# meteo_board.net
KiCad netlist of a schematic drawn in EAGLE
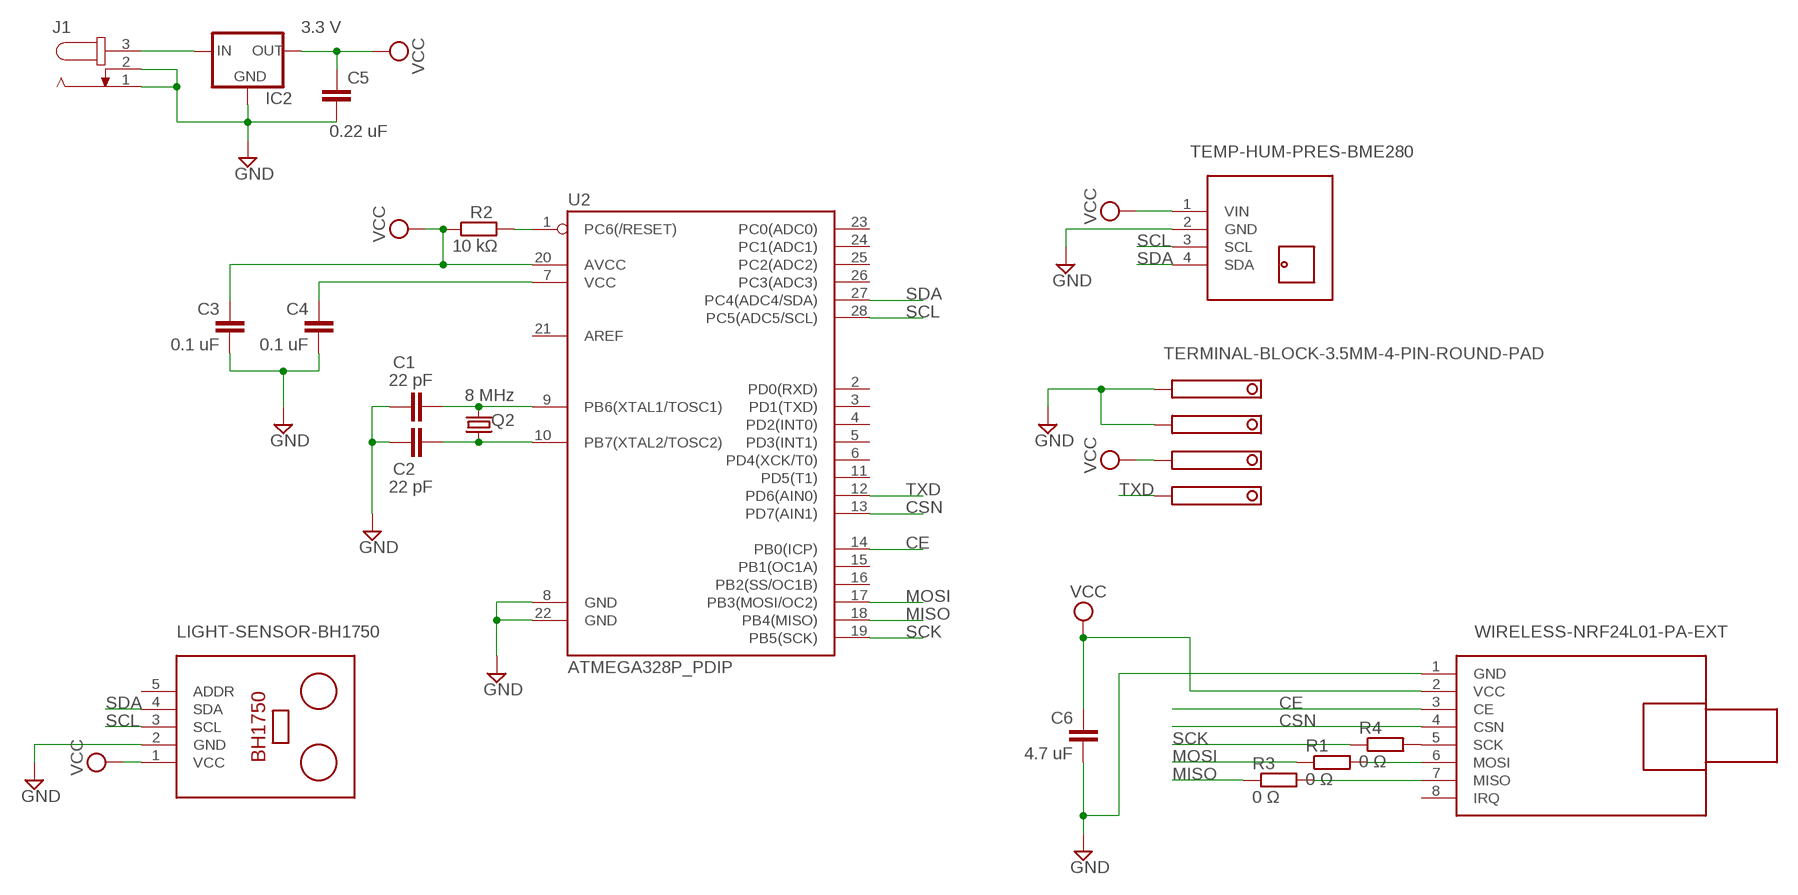
[diagram p0: schematic, sheet 1]

(export (version "E")
  (design (tool "Eeschema 10.0.6"))
  (components
    (comp (ref "C1")
      (value "22 pF")
      (footprint "eagle-import:C2.5-3")
      (libsource (lib "eagle-import") (part "C2,5-3"))
    )
    (comp (ref "C2")
      (value "22 pF")
      (footprint "eagle-import:C2.5-3")
      (libsource (lib "eagle-import") (part "C2,5-3"))
    )
    (comp (ref "C3")
      (value "0.1 uF")
      (footprint "eagle-import:C2.5-3")
      (libsource (lib "eagle-import") (part "C2,5-3"))
    )
    (comp (ref "C4")
      (value "0.1 uF")
      (footprint "eagle-import:C2.5-3")
      (libsource (lib "eagle-import") (part "C2,5-3"))
    )
    (comp (ref "C5")
      (value "0.22 uF")
      (footprint "eagle-import:C2.5-3")
      (libsource (lib "eagle-import") (part "C2,5-3"))
    )
    (comp (ref "C6")
      (value "4.7 uF")
      (footprint "eagle-import:C2.5-3")
      (libsource (lib "eagle-import") (part "C2,5-3"))
    )
    (comp (ref "IC2")
      (value "LFXXCVS")
      (footprint "eagle-import:TO220S")
      (libsource (lib "eagle-import") (part "LFXXCVS"))
    )
    (comp (ref "J1")
      (value "JACK-PLUG0")
      (footprint "eagle-import:SPC4077")
      (libsource (lib "eagle-import") (part "JACK-PLUG0"))
    )
    (comp (ref "M1")
      (value "WIRELESS-NRF24L01-PA-EXT")
      (footprint "eagle-import:WIRELESS-NRF24L01-PA-EXT")
      (libsource (lib "eagle-import") (part "WIRELESS-NRF24L01-PA-EXT"))
    )
    (comp (ref "Q2")
      (value "8 MHz")
      (footprint "eagle-import:HC49_S")
      (libsource (lib "eagle-import") (part "CRYSTALHC49S"))
    )
    (comp (ref "R1")
      (value "0 Ω")
      (footprint "eagle-import:0204_5")
      (libsource (lib "eagle-import") (part "R-EU_0204/5"))
    )
    (comp (ref "R2")
      (value "10 kΩ")
      (footprint "eagle-import:0204_5")
      (libsource (lib "eagle-import") (part "R-EU_0204/5"))
    )
    (comp (ref "R3")
      (value "0 Ω")
      (footprint "eagle-import:0204_5")
      (libsource (lib "eagle-import") (part "R-EU_0204/5"))
    )
    (comp (ref "R4")
      (value "0 Ω")
      (footprint "eagle-import:0204_5")
      (libsource (lib "eagle-import") (part "R-EU_0204/5"))
    )
    (comp (ref "TX20")
      (value "TERMINAL-BLOCK-3.5MM-4-PIN-ROUND-PAD")
      (footprint "eagle-import:TERMINAL-BLOCK-4-PIN-3.5MM-ROUND-PAD")
      (libsource (lib "eagle-import") (part "TERMINAL-BLOCK-3.5MM-4-PIN-ROUND-PAD"))
    )
    (comp (ref "U$5")
      (value "LIGHT-SENSOR-BH1750")
      (footprint "eagle-import:LIGHT-SENSOR-BH1750")
      (libsource (lib "eagle-import") (part "LIGHT-SENSOR-BH1750"))
    )
    (comp (ref "U$6")
      (value "TEMP-HUM-PRES-BME280")
      (footprint "eagle-import:TEMP-HUM-PRES-BME280")
      (libsource (lib "eagle-import") (part "TEMP-HUM-PRES-BME280"))
    )
    (comp (ref "U2")
      (value "ATMEGA328P_PDIP")
      (footprint "eagle-import:DIL28-3")
      (libsource (lib "eagle-import") (part "ATMEGA328P_PDIP"))
    )
  )
  (nets
    (net (code "1") (name "/CE") (class "Default")
      (node (ref "M1") (pin "3") (pinfunction "CE_3") (pintype "bidirectional"))
      (node (ref "U2") (pin "14") (pinfunction "PB0(ICP)_14") (pintype "bidirectional"))
    )
    (net (code "2") (name "/CSN") (class "Default")
      (node (ref "M1") (pin "4") (pinfunction "CSN_4") (pintype "bidirectional"))
      (node (ref "U2") (pin "13") (pinfunction "PD7(AIN1)_13") (pintype "bidirectional"))
    )
    (net (code "3") (name "/MISO") (class "Default")
      (node (ref "R3") (pin "1") (pinfunction "1_1") (pintype "passive"))
      (node (ref "U2") (pin "18") (pinfunction "PB4(MISO)_18") (pintype "bidirectional"))
    )
    (net (code "4") (name "/MOSI") (class "Default")
      (node (ref "R1") (pin "1") (pinfunction "1_1") (pintype "passive"))
      (node (ref "U2") (pin "17") (pinfunction "PB3(MOSI/OC2)_17") (pintype "bidirectional"))
    )
    (net (code "5") (name "/SCK") (class "Default")
      (node (ref "R4") (pin "1") (pinfunction "1_1") (pintype "passive"))
      (node (ref "U2") (pin "19") (pinfunction "PB5(SCK)_19") (pintype "bidirectional"))
    )
    (net (code "6") (name "/SCL") (class "Default")
      (node (ref "U$5") (pin "3") (pinfunction "SCL_3") (pintype "bidirectional"))
      (node (ref "U$6") (pin "3") (pinfunction "SCL_3") (pintype "bidirectional"))
      (node (ref "U2") (pin "28") (pinfunction "PC5(ADC5/SCL)_28") (pintype "bidirectional"))
    )
    (net (code "7") (name "/SDA") (class "Default")
      (node (ref "U$5") (pin "4") (pinfunction "SDA_4") (pintype "bidirectional"))
      (node (ref "U$6") (pin "4") (pinfunction "SDA_4") (pintype "bidirectional"))
      (node (ref "U2") (pin "27") (pinfunction "PC4(ADC4/SDA)_27") (pintype "bidirectional"))
    )
    (net (code "8") (name "/TXD") (class "Default")
      (node (ref "TX20") (pin "4") (pinfunction "K_4") (pintype "passive"))
      (node (ref "U2") (pin "12") (pinfunction "PD6(AIN0)_12") (pintype "bidirectional"))
    )
    (net (code "9") (name "GND") (class "Default")
      (node (ref "C1") (pin "1") (pinfunction "1_1") (pintype "passive"))
      (node (ref "C2") (pin "1") (pinfunction "1_1") (pintype "passive"))
      (node (ref "C3") (pin "1") (pinfunction "1_1") (pintype "passive"))
      (node (ref "C4") (pin "1") (pinfunction "1_1") (pintype "passive"))
      (node (ref "C5") (pin "2") (pinfunction "2_2") (pintype "passive"))
      (node (ref "C6") (pin "1") (pinfunction "1_1") (pintype "passive"))
      (node (ref "IC2") (pin "2") (pinfunction "GND_2") (pintype "input"))
      (node (ref "J1") (pin "1") (pinfunction "1_1") (pintype "passive"))
      (node (ref "J1") (pin "2") (pinfunction "2_2") (pintype "passive"))
      (node (ref "M1") (pin "1") (pinfunction "GND_1") (pintype "power_in"))
      (node (ref "TX20") (pin "1") (pinfunction "K_1") (pintype "passive"))
      (node (ref "TX20") (pin "2") (pinfunction "K_2") (pintype "passive"))
      (node (ref "U$5") (pin "2") (pinfunction "GND_2") (pintype "power_in"))
      (node (ref "U$6") (pin "2") (pinfunction "GND_2") (pintype "power_in"))
      (node (ref "U2") (pin "22") (pinfunction "GND_22") (pintype "bidirectional"))
      (node (ref "U2") (pin "8") (pinfunction "GND_8") (pintype "bidirectional"))
    )
    (net (code "10") (name "Net-(IC2-IN)") (class "Default")
      (node (ref "IC2") (pin "1") (pinfunction "IN_1") (pintype "input"))
      (node (ref "J1") (pin "3") (pinfunction "3_3") (pintype "passive"))
    )
    (net (code "11") (name "Net-(M1-MISO)") (class "Default")
      (node (ref "M1") (pin "7") (pinfunction "MISO_7") (pintype "bidirectional"))
      (node (ref "R3") (pin "2") (pinfunction "2_2") (pintype "passive"))
    )
    (net (code "12") (name "Net-(M1-MOSI)") (class "Default")
      (node (ref "M1") (pin "6") (pinfunction "MOSI_6") (pintype "bidirectional"))
      (node (ref "R1") (pin "2") (pinfunction "2_2") (pintype "passive"))
    )
    (net (code "13") (name "Net-(M1-SCK)") (class "Default")
      (node (ref "M1") (pin "5") (pinfunction "SCK_5") (pintype "bidirectional"))
      (node (ref "R4") (pin "2") (pinfunction "2_2") (pintype "passive"))
    )
    (net (code "14") (name "Net-(U2-PB6(XTAL1{slash}TOSC1))") (class "Default")
      (node (ref "C1") (pin "2") (pinfunction "2_2") (pintype "passive"))
      (node (ref "Q2") (pin "2") (pinfunction "2_2") (pintype "passive"))
      (node (ref "U2") (pin "9") (pinfunction "PB6(XTAL1/TOSC1)_9") (pintype "bidirectional"))
    )
    (net (code "15") (name "Net-(U2-PB7(XTAL2{slash}TOSC2))") (class "Default")
      (node (ref "C2") (pin "2") (pinfunction "2_2") (pintype "passive"))
      (node (ref "Q2") (pin "1") (pinfunction "1_1") (pintype "passive"))
      (node (ref "U2") (pin "10") (pinfunction "PB7(XTAL2/TOSC2)_10") (pintype "bidirectional"))
    )
    (net (code "16") (name "Net-(U2-PC6({slash}RESET))") (class "Default")
      (node (ref "R2") (pin "2") (pinfunction "2_2") (pintype "passive"))
      (node (ref "U2") (pin "1") (pinfunction "PC6(/RESET)_1") (pintype "bidirectional"))
    )
    (net (code "17") (name "Net-(U2-VCC)") (class "Default")
      (node (ref "C4") (pin "2") (pinfunction "2_2") (pintype "passive"))
      (node (ref "U2") (pin "7") (pinfunction "VCC_7") (pintype "bidirectional"))
    )
    (net (code "18") (name "VCC") (class "Default")
      (node (ref "C3") (pin "2") (pinfunction "2_2") (pintype "passive"))
      (node (ref "C5") (pin "1") (pinfunction "1_1") (pintype "passive"))
      (node (ref "C6") (pin "2") (pinfunction "2_2") (pintype "passive"))
      (node (ref "IC2") (pin "3") (pinfunction "OUT_3") (pintype "passive"))
      (node (ref "M1") (pin "2") (pinfunction "VCC_2") (pintype "power_in"))
      (node (ref "R2") (pin "1") (pinfunction "1_1") (pintype "passive"))
      (node (ref "TX20") (pin "3") (pinfunction "K_3") (pintype "passive"))
      (node (ref "U$5") (pin "1") (pinfunction "VCC_1") (pintype "power_in"))
      (node (ref "U$6") (pin "1") (pinfunction "VIN_1") (pintype "power_in"))
      (node (ref "U2") (pin "20") (pinfunction "AVCC_20") (pintype "bidirectional"))
    )
    (net (code "19") (name "unconnected-(M1-IRQ-Pad8)") (class "Default")
      (node (ref "M1") (pin "8") (pinfunction "IRQ_8") (pintype "bidirectional"))
    )
    (net (code "20") (name "unconnected-(U$5-ADDR-Pad5)") (class "Default")
      (node (ref "U$5") (pin "5") (pinfunction "ADDR_5") (pintype "bidirectional"))
    )
    (net (code "21") (name "unconnected-(U2-AREF-Pad21)") (class "Default")
      (node (ref "U2") (pin "21") (pinfunction "AREF_21") (pintype "bidirectional"))
    )
    (net (code "22") (name "unconnected-(U2-PB1(OC1A)-Pad15)") (class "Default")
      (node (ref "U2") (pin "15") (pinfunction "PB1(OC1A)_15") (pintype "bidirectional"))
    )
    (net (code "23") (name "unconnected-(U2-PB2(SS{slash}OC1B)-Pad16)") (class "Default")
      (node (ref "U2") (pin "16") (pinfunction "PB2(SS/OC1B)_16") (pintype "bidirectional"))
    )
    (net (code "24") (name "unconnected-(U2-PC0(ADC0)-Pad23)") (class "Default")
      (node (ref "U2") (pin "23") (pinfunction "PC0(ADC0)_23") (pintype "bidirectional"))
    )
    (net (code "25") (name "unconnected-(U2-PC1(ADC1)-Pad24)") (class "Default")
      (node (ref "U2") (pin "24") (pinfunction "PC1(ADC1)_24") (pintype "bidirectional"))
    )
    (net (code "26") (name "unconnected-(U2-PC2(ADC2)-Pad25)") (class "Default")
      (node (ref "U2") (pin "25") (pinfunction "PC2(ADC2)_25") (pintype "bidirectional"))
    )
    (net (code "27") (name "unconnected-(U2-PC3(ADC3)-Pad26)") (class "Default")
      (node (ref "U2") (pin "26") (pinfunction "PC3(ADC3)_26") (pintype "bidirectional"))
    )
    (net (code "28") (name "unconnected-(U2-PD0(RXD)-Pad2)") (class "Default")
      (node (ref "U2") (pin "2") (pinfunction "PD0(RXD)_2") (pintype "bidirectional"))
    )
    (net (code "29") (name "unconnected-(U2-PD1(TXD)-Pad3)") (class "Default")
      (node (ref "U2") (pin "3") (pinfunction "PD1(TXD)_3") (pintype "bidirectional"))
    )
    (net (code "30") (name "unconnected-(U2-PD2(INT0)-Pad4)") (class "Default")
      (node (ref "U2") (pin "4") (pinfunction "PD2(INT0)_4") (pintype "bidirectional"))
    )
    (net (code "31") (name "unconnected-(U2-PD3(INT1)-Pad5)") (class "Default")
      (node (ref "U2") (pin "5") (pinfunction "PD3(INT1)_5") (pintype "bidirectional"))
    )
    (net (code "32") (name "unconnected-(U2-PD4(XCK{slash}T0)-Pad6)") (class "Default")
      (node (ref "U2") (pin "6") (pinfunction "PD4(XCK/T0)_6") (pintype "bidirectional"))
    )
    (net (code "33") (name "unconnected-(U2-PD5(T1)-Pad11)") (class "Default")
      (node (ref "U2") (pin "11") (pinfunction "PD5(T1)_11") (pintype "bidirectional"))
    )
  )
)
